# Microcontroller.net
KiCad netlist of a schematic drawn in Altium Designer
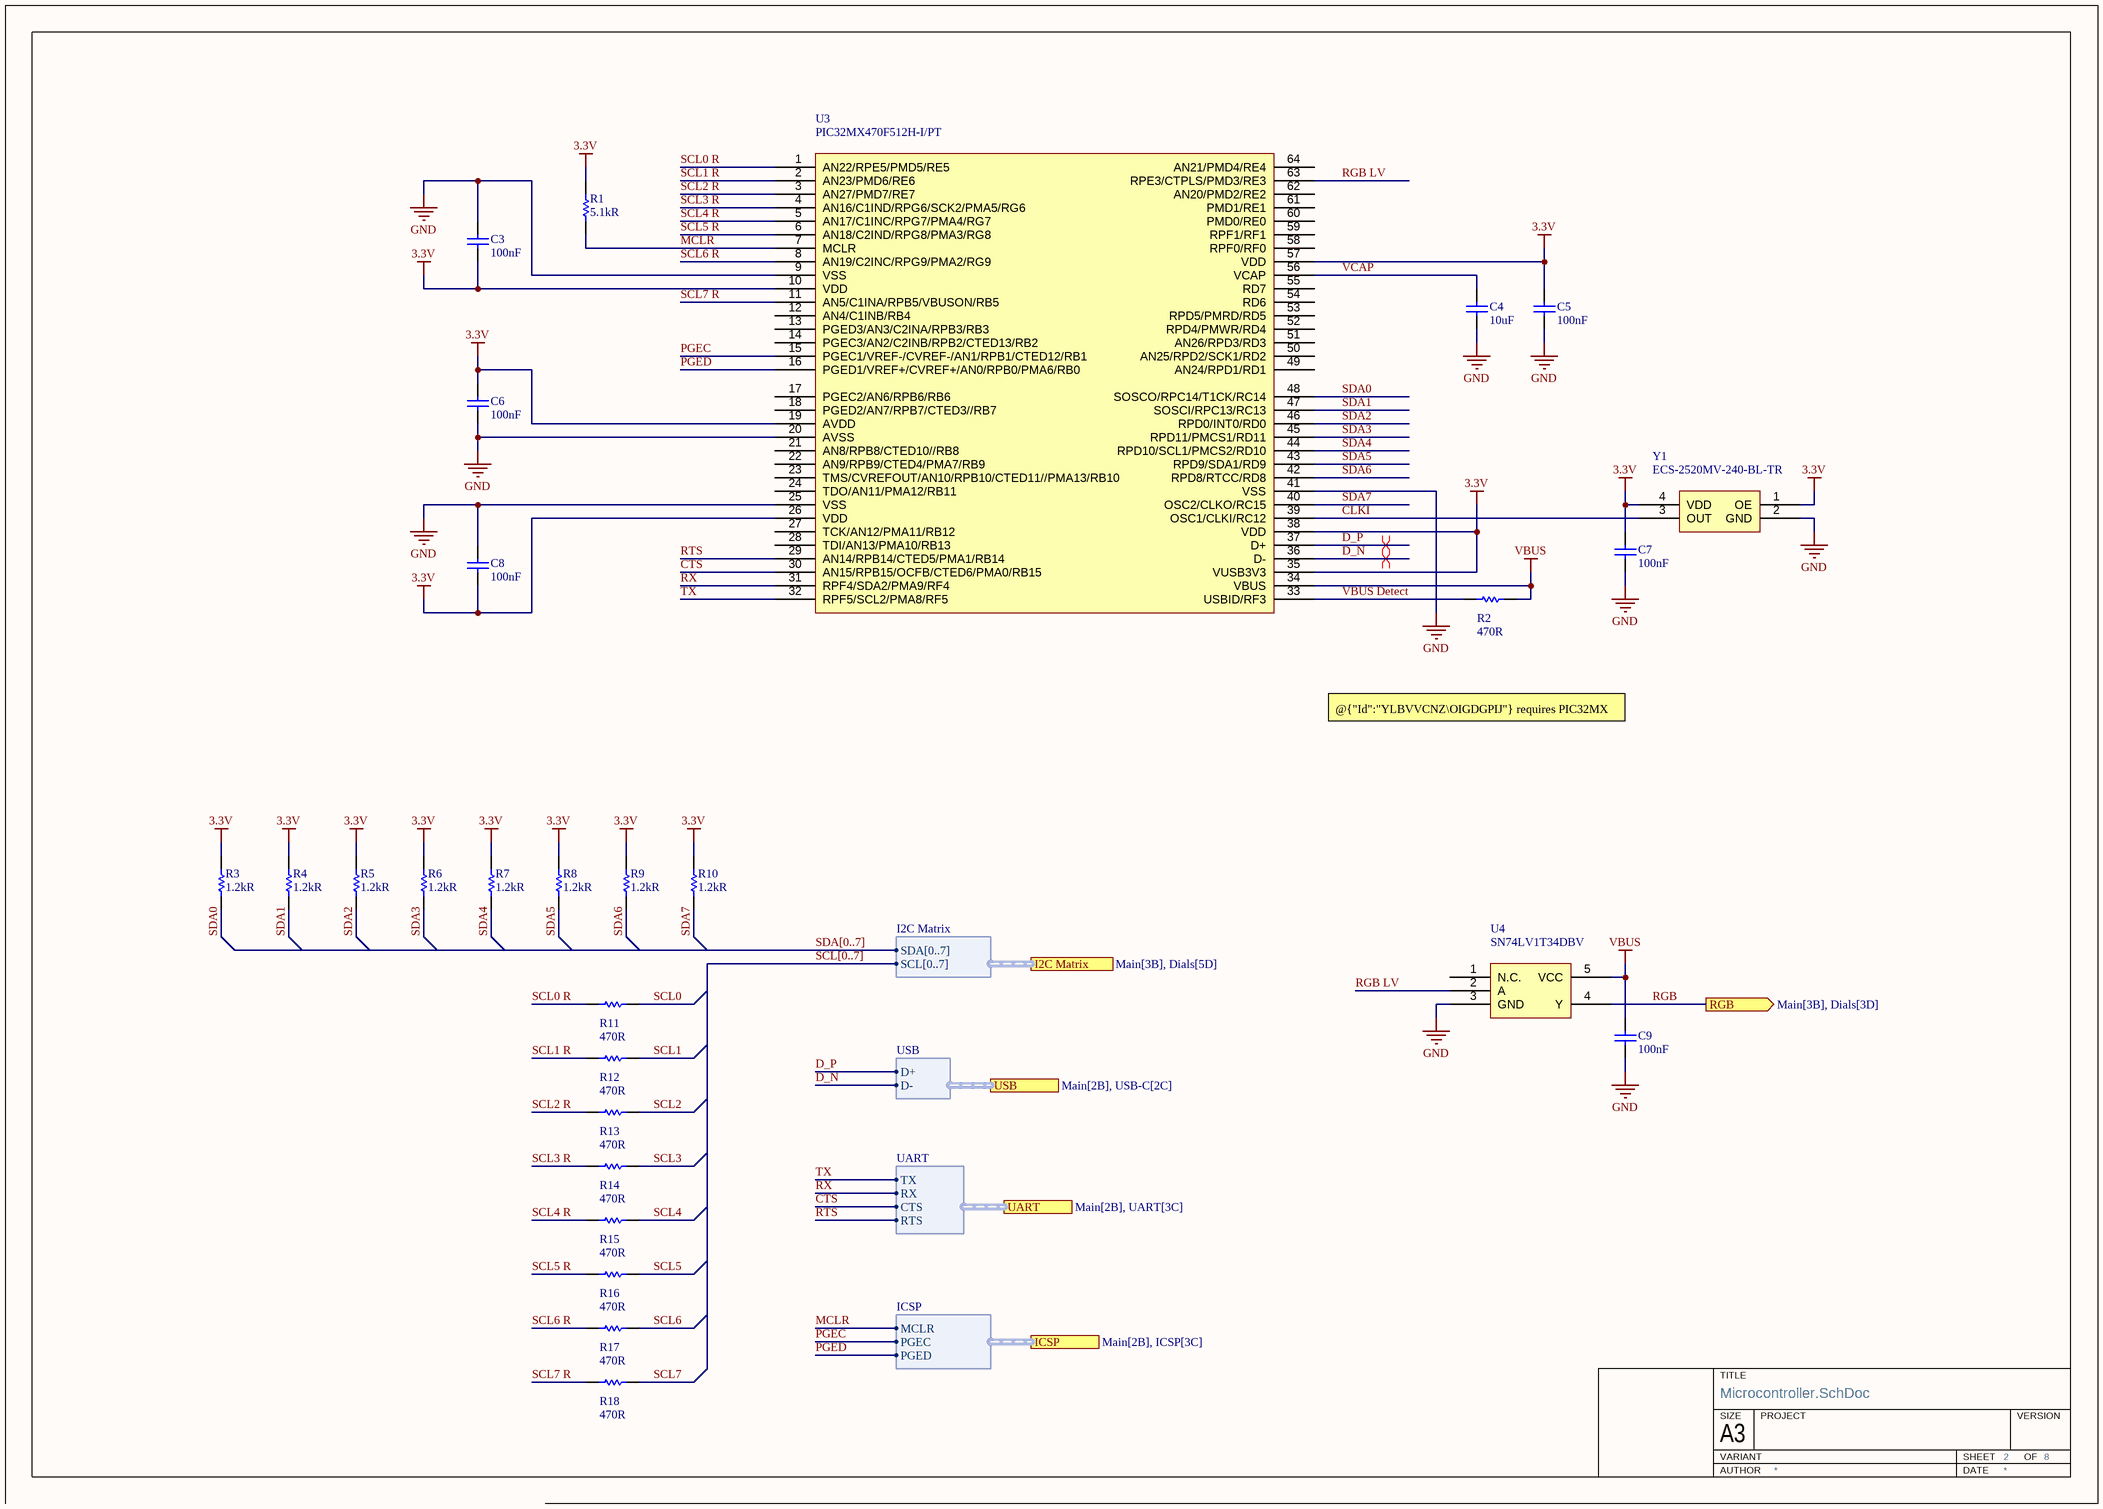
[diagram p0: Microcontroller.SchDoc]

(export (version "E")
  (design (tool "Eeschema 10.0.6"))
  (components
    (comp (ref "C3") (value "100nF") (footprint "Capacitor 0603") (libsource (lib "x-io") (part "Capacitor")))
    (comp (ref "C4") (value "10uF") (footprint "Capacitor 0603") (libsource (lib "x-io") (part "Capacitor")))
    (comp (ref "C5") (value "100nF") (footprint "Capacitor 0603") (libsource (lib "x-io") (part "Capacitor")))
    (comp (ref "C6") (value "100nF") (footprint "Capacitor 0603") (libsource (lib "x-io") (part "Capacitor")))
    (comp (ref "C7") (value "100nF") (footprint "Capacitor 0603") (libsource (lib "x-io") (part "Capacitor")))
    (comp (ref "C8") (value "100nF") (footprint "Capacitor 0603") (libsource (lib "x-io") (part "Capacitor")))
    (comp (ref "C9") (value "100nF") (footprint "Capacitor 0603") (libsource (lib "x-io") (part "Capacitor")))
    (comp (ref "R1") (value "5.1kR") (footprint "Resistor 0603") (libsource (lib "x-io") (part "Resistor")))
    (comp (ref "R2") (value "470R") (footprint "Resistor 0603") (libsource (lib "x-io") (part "Resistor")))
    (comp (ref "R3") (value "1.2kR") (footprint "Resistor 0603") (libsource (lib "x-io") (part "Resistor")))
    (comp (ref "R4") (value "1.2kR") (footprint "Resistor 0603") (libsource (lib "x-io") (part "Resistor")))
    (comp (ref "R5") (value "1.2kR") (footprint "Resistor 0603") (libsource (lib "x-io") (part "Resistor")))
    (comp (ref "R6") (value "1.2kR") (footprint "Resistor 0603") (libsource (lib "x-io") (part "Resistor")))
    (comp (ref "R7") (value "1.2kR") (footprint "Resistor 0603") (libsource (lib "x-io") (part "Resistor")))
    (comp (ref "R8") (value "1.2kR") (footprint "Resistor 0603") (libsource (lib "x-io") (part "Resistor")))
    (comp (ref "R9") (value "1.2kR") (footprint "Resistor 0603") (libsource (lib "x-io") (part "Resistor")))
    (comp (ref "R10") (value "1.2kR") (footprint "Resistor 0603") (libsource (lib "x-io") (part "Resistor")))
    (comp (ref "R11") (value "470R") (footprint "Resistor 0603") (libsource (lib "x-io") (part "Resistor")))
    (comp (ref "R12") (value "470R") (footprint "Resistor 0603") (libsource (lib "x-io") (part "Resistor")))
    (comp (ref "R13") (value "470R") (footprint "Resistor 0603") (libsource (lib "x-io") (part "Resistor")))
    (comp (ref "R14") (value "470R") (footprint "Resistor 0603") (libsource (lib "x-io") (part "Resistor")))
    (comp (ref "R15") (value "470R") (footprint "Resistor 0603") (libsource (lib "x-io") (part "Resistor")))
    (comp (ref "R16") (value "470R") (footprint "Resistor 0603") (libsource (lib "x-io") (part "Resistor")))
    (comp (ref "R17") (value "470R") (footprint "Resistor 0603") (libsource (lib "x-io") (part "Resistor")))
    (comp (ref "R18") (value "470R") (footprint "Resistor 0603") (libsource (lib "x-io") (part "Resistor")))
    (comp (ref "U3")
      (value "PIC32MX470F512H-I/PT")
      (footprint "TQFP-64")
      (libsource (lib "x-io") (part "PIC32MX470F512H"))
    )
    (comp (ref "U4")
      (value "SN74LV1T34DBV")
      (footprint "SOT-23-5")
      (libsource (lib "x-io") (part "SN74LVC1xxx (1 Input)"))
    )
    (comp (ref "Y1")
      (value "ECS-2520MV-240-BL-TR")
      (footprint "ECS-2520MV-240-BL-TR")
      (libsource (lib "x-io") (part "Oscillator"))
    )
  )
  (nets
    (net (code "6") (name "/CLKI") (class "Default")
      (node (ref "U3") (pin "39") (pinfunction "OSC1/CLKI/RC12_39") (pintype "passive"))
      (node (ref "Y1") (pin "3") (pinfunction "OUT_3") (pintype "passive"))
    )
    (net (code "7") (name "/CTS") (class "Default")
      (node (ref "U3") (pin "30") (pinfunction "AN15/RPB15/OCFB/CTED6/PMA0/RB15_30") (pintype "passive"))
    )
    (net (code "8") (name "/D_N") (class "Default")
      (node (ref "U3") (pin "36") (pinfunction "D-_36") (pintype "passive"))
    )
    (net (code "9") (name "/D_P") (class "Default")
      (node (ref "U3") (pin "37") (pinfunction "D+_37") (pintype "passive"))
    )
    (net (code "10") (name "/MCLR") (class "Default")
      (node (ref "R1") (pin "1") (pinfunction "1_1") (pintype "passive"))
      (node (ref "U3") (pin "7") (pinfunction "MCLR_7") (pintype "passive"))
    )
    (net (code "11") (name "/PGEC") (class "Default")
      (node (ref "U3") (pin "15") (pinfunction "PGEC1/VREF-/CVREF-/AN1/RPB1/CTED12/RB1_15") (pintype "passive"))
    )
    (net (code "12") (name "/PGED") (class "Default")
      (node (ref "U3") (pin "16") (pinfunction "PGED1/VREF+/CVREF+/AN0/RPB0/PMA6/RB0_16") (pintype "passive"))
    )
    (net (code "13") (name "/RGB") (class "Default")
      (node (ref "U4") (pin "4") (pinfunction "Y_4") (pintype "passive"))
    )
    (net (code "14") (name "/RGB LV") (class "Default")
      (node (ref "U3") (pin "63") (pinfunction "RPE3/CTPLS/PMD3/RE3_63") (pintype "passive"))
      (node (ref "U4") (pin "2") (pinfunction "A_2") (pintype "passive"))
    )
    (net (code "15") (name "/RTS") (class "Default")
      (node (ref "U3") (pin "29") (pinfunction "AN14/RPB14/CTED5/PMA1/RB14_29") (pintype "passive"))
    )
    (net (code "16") (name "/RX") (class "Default")
      (node (ref "U3") (pin "31") (pinfunction "RPF4/SDA2/PMA9/RF4_31") (pintype "passive"))
    )
    (net (code "17") (name "/SCL0") (class "Default")
      (node (ref "R11") (pin "2") (pinfunction "2_2") (pintype "passive"))
    )
    (net (code "18") (name "/SCL0 R") (class "Default")
      (node (ref "R11") (pin "1") (pinfunction "1_1") (pintype "passive"))
      (node (ref "U3") (pin "1") (pinfunction "AN22/RPE5/PMD5/RE5_1") (pintype "passive"))
    )
    (net (code "19") (name "/SCL1") (class "Default")
      (node (ref "R12") (pin "2") (pinfunction "2_2") (pintype "passive"))
    )
    (net (code "20") (name "/SCL1 R") (class "Default")
      (node (ref "R12") (pin "1") (pinfunction "1_1") (pintype "passive"))
      (node (ref "U3") (pin "2") (pinfunction "AN23/PMD6/RE6_2") (pintype "passive"))
    )
    (net (code "21") (name "/SCL2") (class "Default")
      (node (ref "R13") (pin "2") (pinfunction "2_2") (pintype "passive"))
    )
    (net (code "22") (name "/SCL2 R") (class "Default")
      (node (ref "R13") (pin "1") (pinfunction "1_1") (pintype "passive"))
      (node (ref "U3") (pin "3") (pinfunction "AN27/PMD7/RE7_3") (pintype "passive"))
    )
    (net (code "23") (name "/SCL3") (class "Default")
      (node (ref "R14") (pin "2") (pinfunction "2_2") (pintype "passive"))
    )
    (net (code "24") (name "/SCL3 R") (class "Default")
      (node (ref "R14") (pin "1") (pinfunction "1_1") (pintype "passive"))
      (node (ref "U3") (pin "4") (pinfunction "AN16/C1IND/RPG6/SCK2/PMA5/RG6_4") (pintype "passive"))
    )
    (net (code "25") (name "/SCL4") (class "Default")
      (node (ref "R15") (pin "2") (pinfunction "2_2") (pintype "passive"))
    )
    (net (code "26") (name "/SCL4 R") (class "Default")
      (node (ref "R15") (pin "1") (pinfunction "1_1") (pintype "passive"))
      (node (ref "U3") (pin "5") (pinfunction "AN17/C1INC/RPG7/PMA4/RG7_5") (pintype "passive"))
    )
    (net (code "27") (name "/SCL5") (class "Default")
      (node (ref "R16") (pin "2") (pinfunction "2_2") (pintype "passive"))
    )
    (net (code "28") (name "/SCL5 R") (class "Default")
      (node (ref "R16") (pin "1") (pinfunction "1_1") (pintype "passive"))
      (node (ref "U3") (pin "6") (pinfunction "AN18/C2IND/RPG8/PMA3/RG8_6") (pintype "passive"))
    )
    (net (code "29") (name "/SCL6") (class "Default")
      (node (ref "R17") (pin "2") (pinfunction "2_2") (pintype "passive"))
    )
    (net (code "30") (name "/SCL6 R") (class "Default")
      (node (ref "R17") (pin "1") (pinfunction "1_1") (pintype "passive"))
      (node (ref "U3") (pin "8") (pinfunction "AN19/C2INC/RPG9/PMA2/RG9_8") (pintype "passive"))
    )
    (net (code "31") (name "/SCL7") (class "Default")
      (node (ref "R18") (pin "2") (pinfunction "2_2") (pintype "passive"))
    )
    (net (code "32") (name "/SCL7 R") (class "Default")
      (node (ref "R18") (pin "1") (pinfunction "1_1") (pintype "passive"))
      (node (ref "U3") (pin "11") (pinfunction "AN5/C1INA/RPB5/VBUSON/RB5_11") (pintype "passive"))
    )
    (net (code "34") (name "/SDA0") (class "Default")
      (node (ref "R3") (pin "1") (pinfunction "1_1") (pintype "passive"))
      (node (ref "U3") (pin "48") (pinfunction "SOSCO/RPC14/T1CK/RC14_48") (pintype "passive"))
    )
    (net (code "35") (name "/SDA1") (class "Default")
      (node (ref "R4") (pin "1") (pinfunction "1_1") (pintype "passive"))
      (node (ref "U3") (pin "47") (pinfunction "SOSCI/RPC13/RC13_47") (pintype "passive"))
    )
    (net (code "36") (name "/SDA2") (class "Default")
      (node (ref "R5") (pin "1") (pinfunction "1_1") (pintype "passive"))
      (node (ref "U3") (pin "46") (pinfunction "RPD0/INT0/RD0_46") (pintype "passive"))
    )
    (net (code "37") (name "/SDA3") (class "Default")
      (node (ref "R6") (pin "1") (pinfunction "1_1") (pintype "passive"))
      (node (ref "U3") (pin "45") (pinfunction "RPD11/PMCS1/RD11_45") (pintype "passive"))
    )
    (net (code "38") (name "/SDA4") (class "Default")
      (node (ref "R7") (pin "1") (pinfunction "1_1") (pintype "passive"))
      (node (ref "U3") (pin "44") (pinfunction "RPD10/SCL1/PMCS2/RD10_44") (pintype "passive"))
    )
    (net (code "39") (name "/SDA5") (class "Default")
      (node (ref "R8") (pin "1") (pinfunction "1_1") (pintype "passive"))
      (node (ref "U3") (pin "43") (pinfunction "RPD9/SDA1/RD9_43") (pintype "passive"))
    )
    (net (code "40") (name "/SDA6") (class "Default")
      (node (ref "R9") (pin "1") (pinfunction "1_1") (pintype "passive"))
      (node (ref "U3") (pin "42") (pinfunction "RPD8/RTCC/RD8_42") (pintype "passive"))
    )
    (net (code "41") (name "/SDA7") (class "Default")
      (node (ref "R10") (pin "1") (pinfunction "1_1") (pintype "passive"))
      (node (ref "U3") (pin "40") (pinfunction "OSC2/CLKO/RC15_40") (pintype "passive"))
    )
    (net (code "43") (name "/TX") (class "Default")
      (node (ref "U3") (pin "32") (pinfunction "RPF5/SCL2/PMA8/RF5_32") (pintype "passive"))
    )
    (net (code "44") (name "/VBUS Detect") (class "Default")
      (node (ref "R2") (pin "1") (pinfunction "1_1") (pintype "passive"))
      (node (ref "U3") (pin "33") (pinfunction "USBID/RF3_33") (pintype "passive"))
    )
    (net (code "45") (name "/VCAP") (class "Default")
      (node (ref "C4") (pin "2") (pinfunction "2_2") (pintype "passive"))
      (node (ref "U3") (pin "56") (pinfunction "VCAP_56") (pintype "passive"))
    )
    (net (code "50") (name "3.3V") (class "Default")
      (node (ref "C3") (pin "1") (pinfunction "1_1") (pintype "passive"))
      (node (ref "C5") (pin "2") (pinfunction "2_2") (pintype "passive"))
      (node (ref "C6") (pin "2") (pinfunction "2_2") (pintype "passive"))
      (node (ref "C7") (pin "2") (pinfunction "2_2") (pintype "passive"))
      (node (ref "C8") (pin "1") (pinfunction "1_1") (pintype "passive"))
      (node (ref "R1") (pin "2") (pinfunction "2_2") (pintype "passive"))
      (node (ref "R10") (pin "2") (pinfunction "2_2") (pintype "passive"))
      (node (ref "R3") (pin "2") (pinfunction "2_2") (pintype "passive"))
      (node (ref "R4") (pin "2") (pinfunction "2_2") (pintype "passive"))
      (node (ref "R5") (pin "2") (pinfunction "2_2") (pintype "passive"))
      (node (ref "R6") (pin "2") (pinfunction "2_2") (pintype "passive"))
      (node (ref "R7") (pin "2") (pinfunction "2_2") (pintype "passive"))
      (node (ref "R8") (pin "2") (pinfunction "2_2") (pintype "passive"))
      (node (ref "R9") (pin "2") (pinfunction "2_2") (pintype "passive"))
      (node (ref "U3") (pin "10") (pinfunction "VDD_10") (pintype "passive"))
      (node (ref "U3") (pin "19") (pinfunction "AVDD_19") (pintype "passive"))
      (node (ref "U3") (pin "26") (pinfunction "VDD_26") (pintype "passive"))
      (node (ref "U3") (pin "35") (pinfunction "VUSB3V3_35") (pintype "passive"))
      (node (ref "U3") (pin "38") (pinfunction "VDD_38") (pintype "passive"))
      (node (ref "U3") (pin "57") (pinfunction "VDD_57") (pintype "passive"))
      (node (ref "Y1") (pin "1") (pinfunction "OE_1") (pintype "passive"))
      (node (ref "Y1") (pin "4") (pinfunction "VDD_4") (pintype "passive"))
    )
    (net (code "51") (name "GND") (class "Default")
      (node (ref "C3") (pin "2") (pinfunction "2_2") (pintype "passive"))
      (node (ref "C4") (pin "1") (pinfunction "1_1") (pintype "passive"))
      (node (ref "C5") (pin "1") (pinfunction "1_1") (pintype "passive"))
      (node (ref "C6") (pin "1") (pinfunction "1_1") (pintype "passive"))
      (node (ref "C7") (pin "1") (pinfunction "1_1") (pintype "passive"))
      (node (ref "C8") (pin "2") (pinfunction "2_2") (pintype "passive"))
      (node (ref "C9") (pin "1") (pinfunction "1_1") (pintype "passive"))
      (node (ref "U3") (pin "20") (pinfunction "AVSS_20") (pintype "passive"))
      (node (ref "U3") (pin "25") (pinfunction "VSS_25") (pintype "passive"))
      (node (ref "U3") (pin "41") (pinfunction "VSS_41") (pintype "passive"))
      (node (ref "U3") (pin "9") (pinfunction "VSS_9") (pintype "passive"))
      (node (ref "U4") (pin "3") (pinfunction "GND_3") (pintype "passive"))
      (node (ref "Y1") (pin "2") (pinfunction "GND_2") (pintype "passive"))
    )
    (net (code "52") (name "VBUS") (class "Default")
      (node (ref "C9") (pin "2") (pinfunction "2_2") (pintype "passive"))
      (node (ref "R2") (pin "2") (pinfunction "2_2") (pintype "passive"))
      (node (ref "U3") (pin "34") (pinfunction "VBUS_34") (pintype "passive"))
      (node (ref "U4") (pin "5") (pinfunction "VCC_5") (pintype "passive"))
    )
    (net (code "53") (name "unconnected-(U3-AN4{slash}C1INB{slash}RB4-Pad12)") (class "Default")
      (node (ref "U3") (pin "12") (pinfunction "AN4/C1INB/RB4_12") (pintype "passive"))
    )
    (net (code "54") (name "unconnected-(U3-AN8{slash}RPB8{slash}CTED10{slash}{slash}RB8-Pad21)") (class "Default")
      (node (ref "U3") (pin "21") (pinfunction "AN8/RPB8/CTED10//RB8_21") (pintype "passive"))
    )
    (net (code "55") (name "unconnected-(U3-AN9{slash}RPB9{slash}CTED4{slash}PMA7{slash}RB9-Pad22)") (class "Default")
      (node (ref "U3") (pin "22") (pinfunction "AN9/RPB9/CTED4/PMA7/RB9_22") (pintype "passive"))
    )
    (net (code "56") (name "unconnected-(U3-AN20{slash}PMD2{slash}RE2-Pad62)") (class "Default")
      (node (ref "U3") (pin "62") (pinfunction "AN20/PMD2/RE2_62") (pintype "passive"))
    )
    (net (code "57") (name "unconnected-(U3-AN21{slash}PMD4{slash}RE4-Pad64)") (class "Default")
      (node (ref "U3") (pin "64") (pinfunction "AN21/PMD4/RE4_64") (pintype "passive"))
    )
    (net (code "58") (name "unconnected-(U3-AN24{slash}RPD1{slash}RD1-Pad49)") (class "Default")
      (node (ref "U3") (pin "49") (pinfunction "AN24/RPD1/RD1_49") (pintype "passive"))
    )
    (net (code "59") (name "unconnected-(U3-AN25{slash}RPD2{slash}SCK1{slash}RD2-Pad50)") (class "Default")
      (node (ref "U3") (pin "50") (pinfunction "AN25/RPD2/SCK1/RD2_50") (pintype "passive"))
    )
    (net (code "60") (name "unconnected-(U3-AN26{slash}RPD3{slash}RD3-Pad51)") (class "Default")
      (node (ref "U3") (pin "51") (pinfunction "AN26/RPD3/RD3_51") (pintype "passive"))
    )
    (net (code "61") (name "unconnected-(U3-PGEC2{slash}AN6{slash}RPB6{slash}RB6-Pad17)") (class "Default")
      (node (ref "U3") (pin "17") (pinfunction "PGEC2/AN6/RPB6/RB6_17") (pintype "passive"))
    )
    (net (code "62") (name "unconnected-(U3-PGEC3{slash}AN2{slash}C2INB{slash}RPB2{slash}CTED13{slash}RB2-Pad14)") (class "Default")
      (node (ref "U3") (pin "14") (pinfunction "PGEC3/AN2/C2INB/RPB2/CTED13/RB2_14") (pintype "passive"))
    )
    (net (code "63") (name "unconnected-(U3-PGED2{slash}AN7{slash}RPB7{slash}CTED3{slash}{slash}RB7-Pad18)") (class "Default")
      (node (ref "U3") (pin "18") (pinfunction "PGED2/AN7/RPB7/CTED3//RB7_18") (pintype "passive"))
    )
    (net (code "64") (name "unconnected-(U3-PGED3{slash}AN3{slash}C2INA{slash}RPB3{slash}RB3-Pad13)") (class "Default")
      (node (ref "U3") (pin "13") (pinfunction "PGED3/AN3/C2INA/RPB3/RB3_13") (pintype "passive"))
    )
    (net (code "65") (name "unconnected-(U3-PMD0{slash}RE0-Pad60)") (class "Default")
      (node (ref "U3") (pin "60") (pinfunction "PMD0/RE0_60") (pintype "passive"))
    )
    (net (code "66") (name "unconnected-(U3-PMD1{slash}RE1-Pad61)") (class "Default")
      (node (ref "U3") (pin "61") (pinfunction "PMD1/RE1_61") (pintype "passive"))
    )
    (net (code "67") (name "unconnected-(U3-RD6-Pad54)") (class "Default")
      (node (ref "U3") (pin "54") (pinfunction "RD6_54") (pintype "passive"))
    )
    (net (code "68") (name "unconnected-(U3-RD7-Pad55)") (class "Default")
      (node (ref "U3") (pin "55") (pinfunction "RD7_55") (pintype "passive"))
    )
    (net (code "69") (name "unconnected-(U3-RPD4{slash}PMWR{slash}RD4-Pad52)") (class "Default")
      (node (ref "U3") (pin "52") (pinfunction "RPD4/PMWR/RD4_52") (pintype "passive"))
    )
    (net (code "70") (name "unconnected-(U3-RPD5{slash}PMRD{slash}RD5-Pad53)") (class "Default")
      (node (ref "U3") (pin "53") (pinfunction "RPD5/PMRD/RD5_53") (pintype "passive"))
    )
    (net (code "71") (name "unconnected-(U3-RPF0{slash}RF0-Pad58)") (class "Default")
      (node (ref "U3") (pin "58") (pinfunction "RPF0/RF0_58") (pintype "passive"))
    )
    (net (code "72") (name "unconnected-(U3-RPF1{slash}RF1-Pad59)") (class "Default")
      (node (ref "U3") (pin "59") (pinfunction "RPF1/RF1_59") (pintype "passive"))
    )
    (net (code "73") (name "unconnected-(U3-TCK{slash}AN12{slash}PMA11{slash}RB12-Pad27)") (class "Default")
      (node (ref "U3") (pin "27") (pinfunction "TCK/AN12/PMA11/RB12_27") (pintype "passive"))
    )
    (net (code "74") (name "unconnected-(U3-TDI{slash}AN13{slash}PMA10{slash}RB13-Pad28)") (class "Default")
      (node (ref "U3") (pin "28") (pinfunction "TDI/AN13/PMA10/RB13_28") (pintype "passive"))
    )
    (net (code "75") (name "unconnected-(U3-TDO{slash}AN11{slash}PMA12{slash}RB11-Pad24)") (class "Default")
      (node (ref "U3") (pin "24") (pinfunction "TDO/AN11/PMA12/RB11_24") (pintype "passive"))
    )
    (net (code "76") (name "unconnected-(U3-TMS{slash}CVREFOUT{slash}AN10{slash}RPB10{slash}CTED11{slash}{slash}PMA13{slash}RB10-Pad23)") (class "Default")
      (node (ref "U3") (pin "23") (pinfunction "TMS/CVREFOUT/AN10/RPB10/CTED11//PMA13/RB10_23") (pintype "passive"))
    )
    (net (code "77") (name "unconnected-(U4-N.C.-Pad1)") (class "Default")
      (node (ref "U4") (pin "1") (pinfunction "N.C._1") (pintype "passive"))
    )
  )
)
